# solar_charger_fuel_gauge_dev.net
KiCad netlist of a schematic drawn in EAGLE
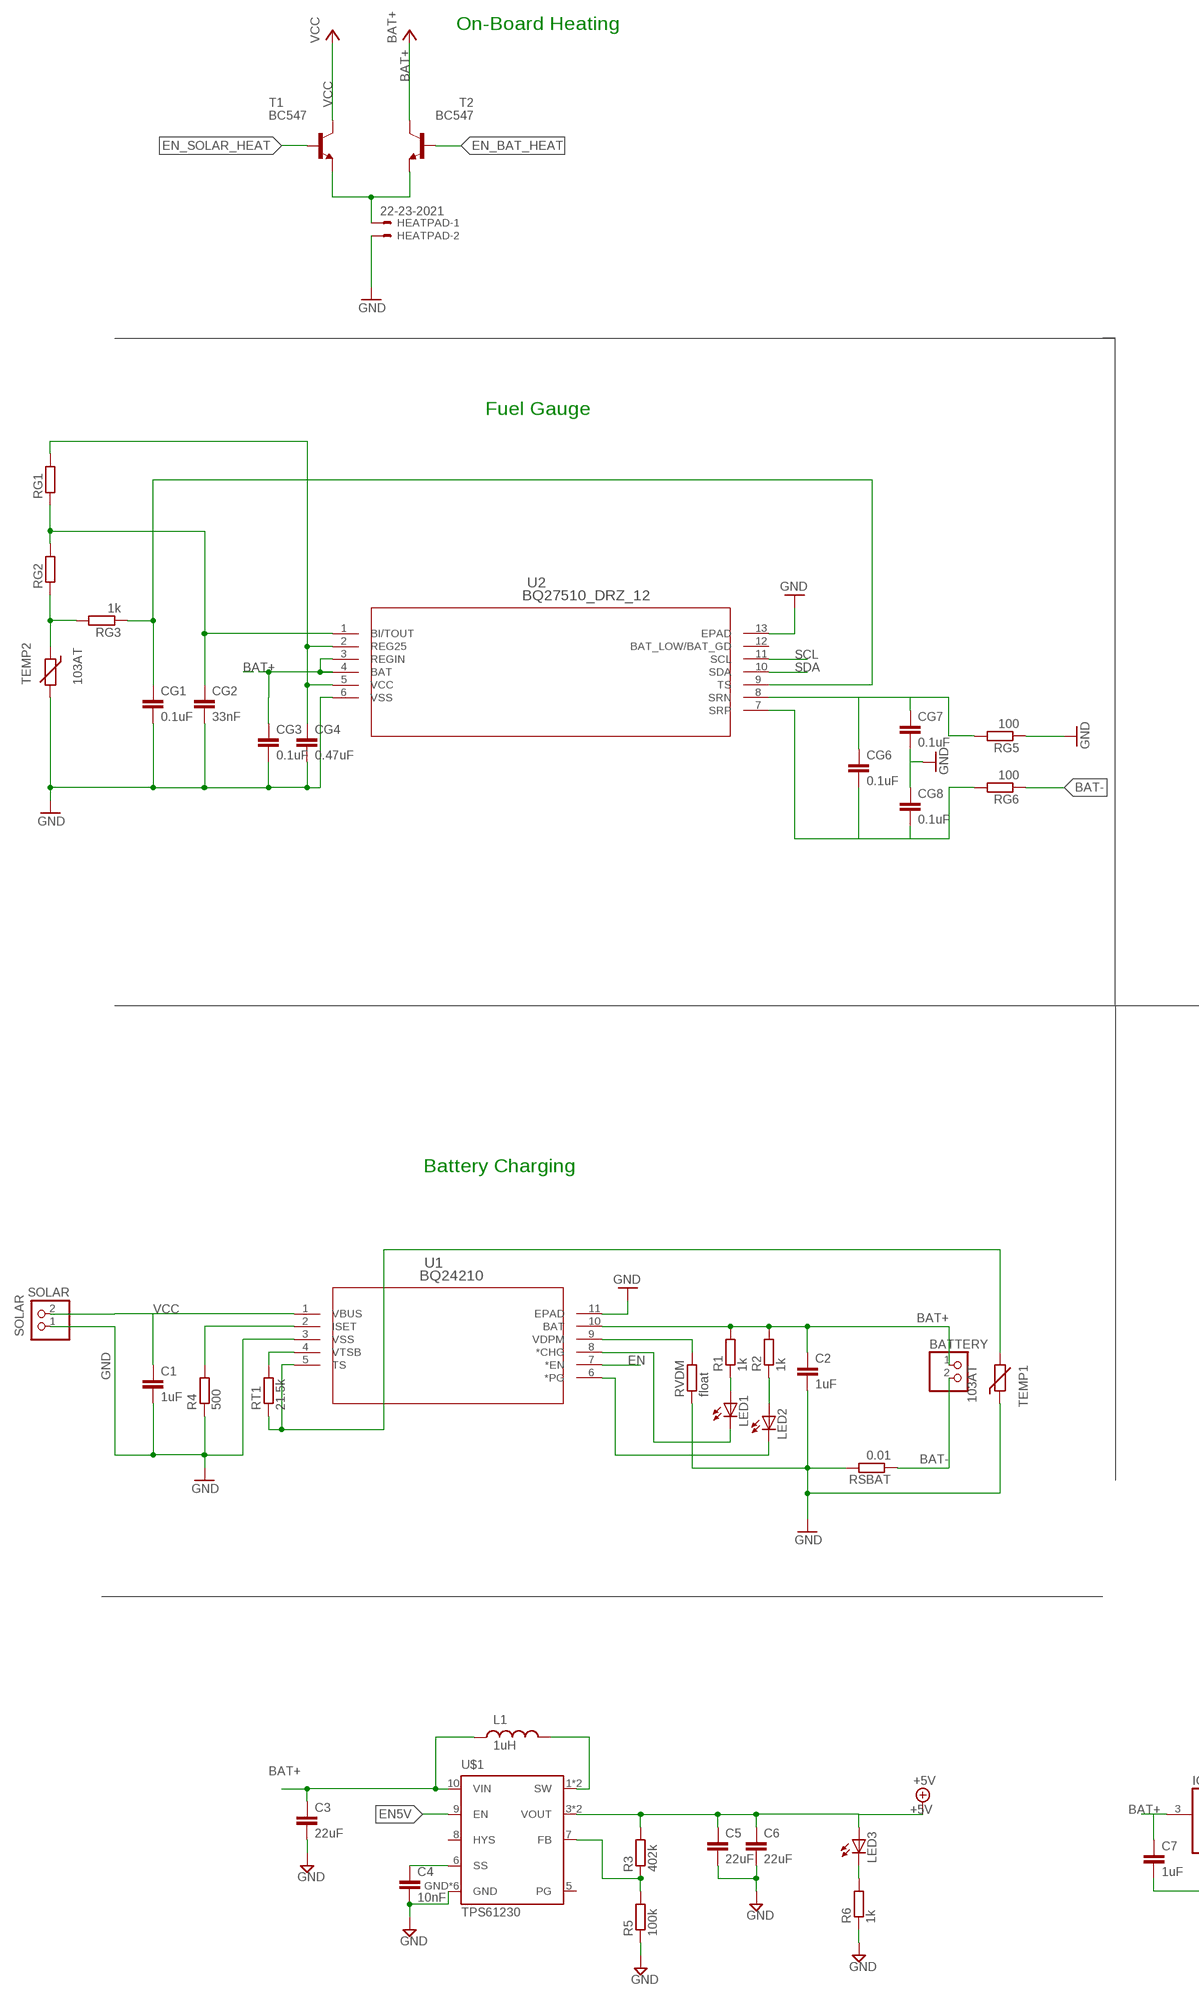
[diagram p0: schematic, sheet 1, part 1 of 3]
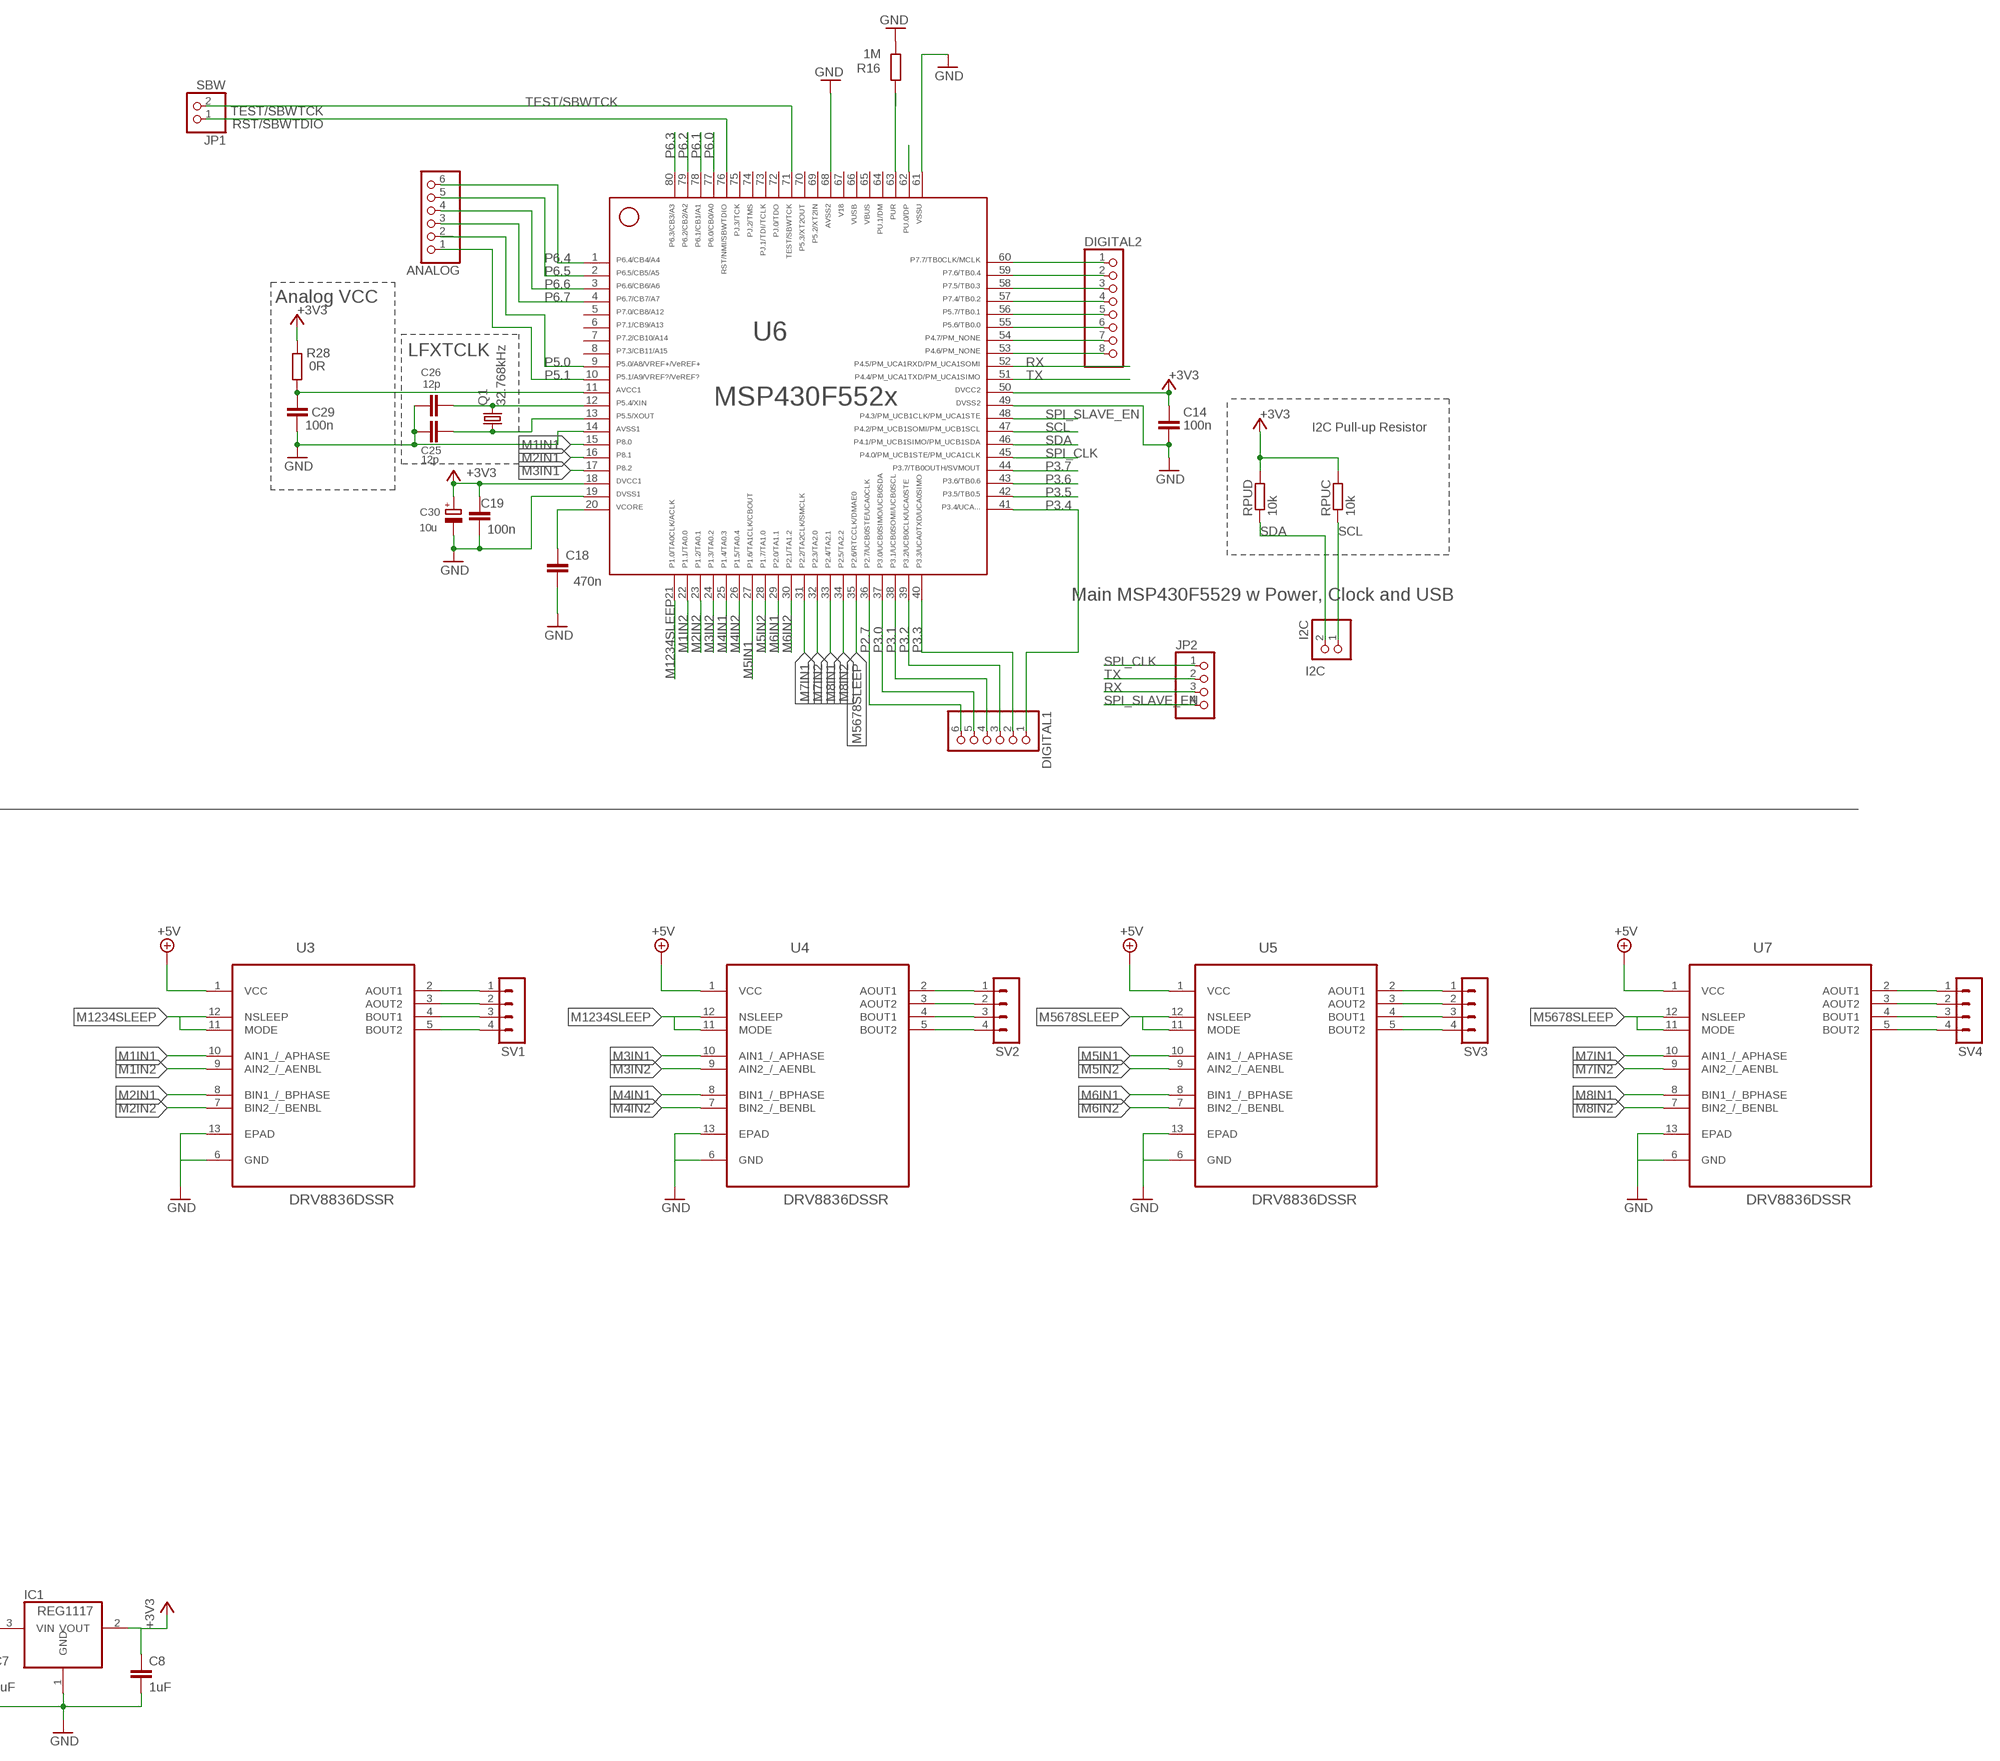
[diagram p1: schematic, sheet 1, part 2 of 3]
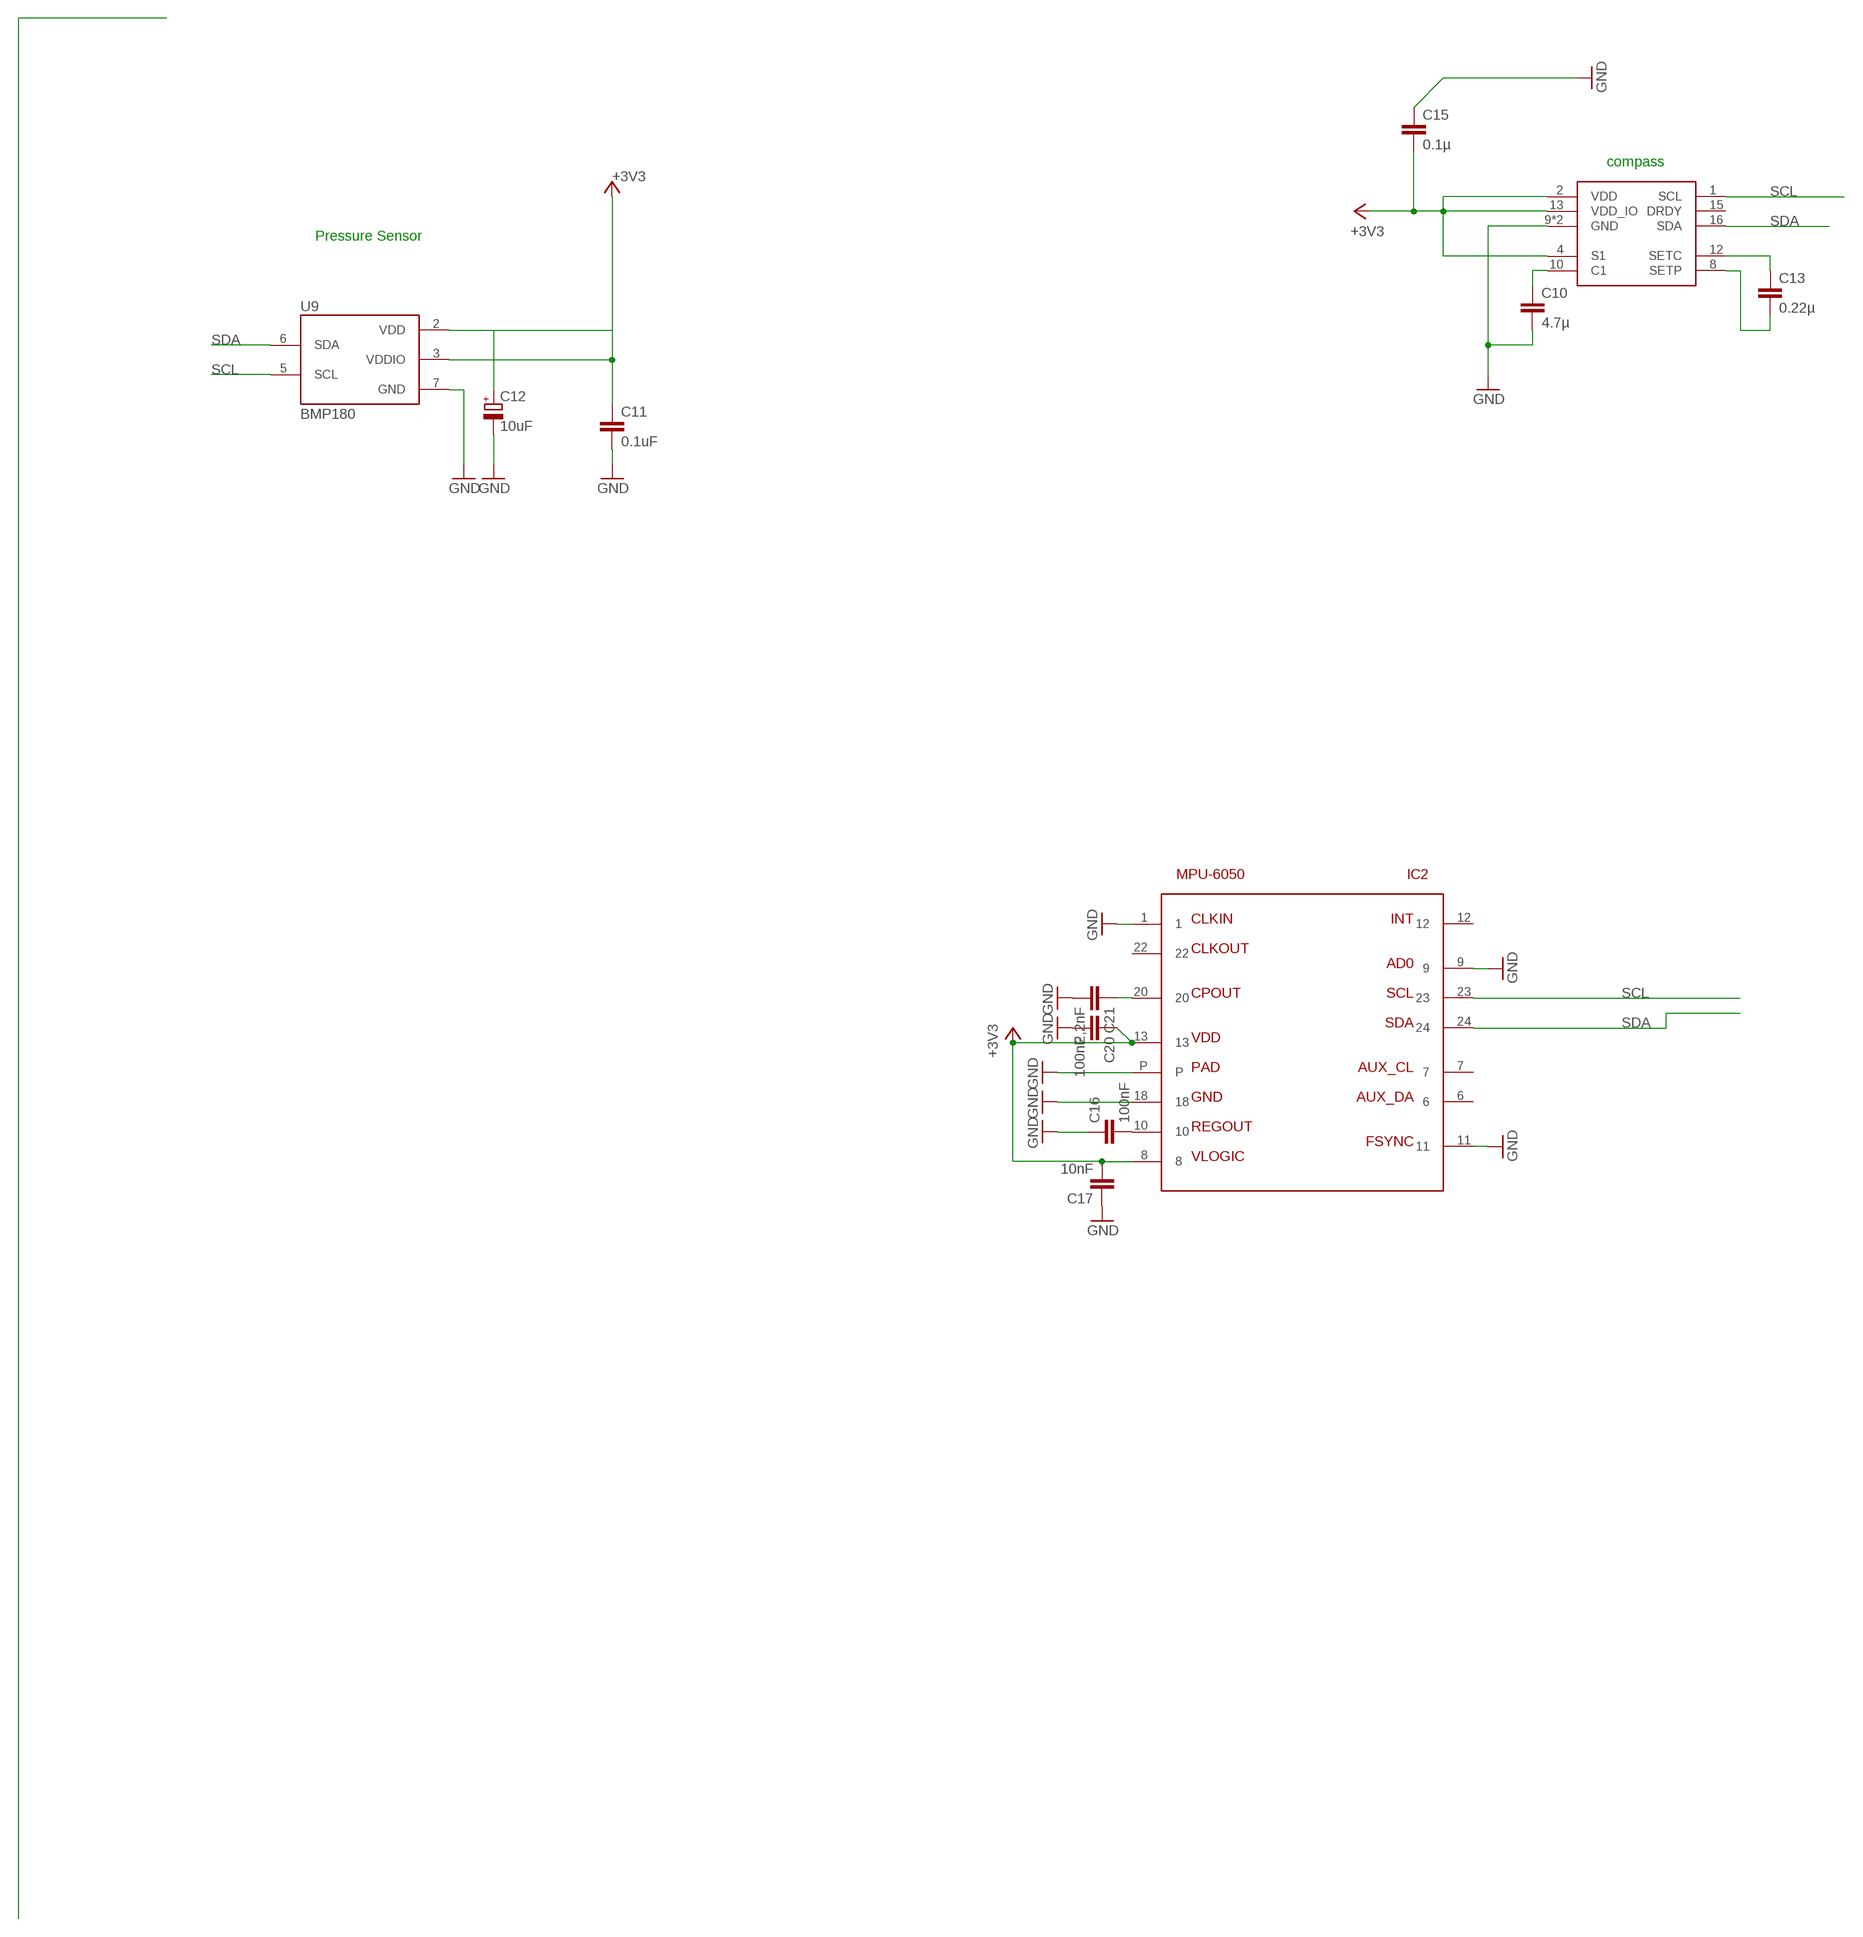
[diagram p2: schematic, sheet 1, part 3 of 3]

(export (version "E")
  (design (tool "Eeschema 10.0.6"))
  (components
    (comp (ref "ANALOG")
      (value "PINHD-1X6")
      (footprint "eagle-import:1X06")
      (libsource (lib "eagle-import") (part "PINHD-1X6"))
    )
    (comp (ref "BATTERY")
      (value "PINHD-1X2")
      (footprint "eagle-import:1X02")
      (libsource (lib "eagle-import") (part "PINHD-1X2"))
    )
    (comp (ref "C1")
      (value "1uF")
      (footprint "eagle-import:C1206")
      (libsource (lib "eagle-import") (part "C-EUC1206"))
    )
    (comp (ref "C2")
      (value "1uF")
      (footprint "eagle-import:C1206")
      (libsource (lib "eagle-import") (part "C-EUC1206"))
    )
    (comp (ref "C3")
      (value "22uF")
      (footprint "eagle-import:C0603")
      (libsource (lib "eagle-import") (part "C-EUC0603"))
    )
    (comp (ref "C4")
      (value "10nF")
      (footprint "eagle-import:C0603")
      (libsource (lib "eagle-import") (part "C-EUC0603"))
    )
    (comp (ref "C5")
      (value "22uF")
      (footprint "eagle-import:C0603")
      (libsource (lib "eagle-import") (part "C-EUC0603"))
    )
    (comp (ref "C6")
      (value "22uF")
      (footprint "eagle-import:C0603")
      (libsource (lib "eagle-import") (part "C-EUC0603"))
    )
    (comp (ref "C7")
      (value "1uF")
      (footprint "eagle-import:C0603")
      (libsource (lib "eagle-import") (part "C-EUC0603"))
    )
    (comp (ref "C8")
      (value "1uF")
      (footprint "eagle-import:C0603")
      (libsource (lib "eagle-import") (part "C-EUC0603"))
    )
    (comp (ref "C10")
      (value "4.7µ")
      (footprint "eagle-import:C0603")
      (libsource (lib "eagle-import") (part "C-EUC0603"))
    )
    (comp (ref "C11")
      (value "0.1uF")
      (footprint "eagle-import:C0603")
      (libsource (lib "eagle-import") (part "C-EUC0603"))
    )
    (comp (ref "C12")
      (value "10uF")
      (footprint "eagle-import:A_3216-18R")
      (libsource (lib "eagle-import") (part "resistor_CPOL-EUA/3216-18R"))
    )
    (comp (ref "C13")
      (value "0.22µ")
      (footprint "eagle-import:C0603")
      (libsource (lib "eagle-import") (part "C-EUC0603"))
    )
    (comp (ref "C14")
      (value "100n")
      (footprint "eagle-import:C0603")
      (libsource (lib "eagle-import") (part "C-EUC0603"))
    )
    (comp (ref "C15")
      (value "0.1µ")
      (footprint "eagle-import:C0603")
      (libsource (lib "eagle-import") (part "C-EUC0603"))
    )
    (comp (ref "C16")
      (value "100nF")
      (footprint "eagle-import:C0603")
      (libsource (lib "eagle-import") (part "C-EUC0603"))
    )
    (comp (ref "C17")
      (value "10nF")
      (footprint "eagle-import:C0603")
      (libsource (lib "eagle-import") (part "C-EUC0603"))
    )
    (comp (ref "C18")
      (value "470n")
      (footprint "eagle-import:C0603")
      (libsource (lib "eagle-import") (part "C-EUC0603"))
    )
    (comp (ref "C19")
      (value "100n")
      (footprint "eagle-import:C0603")
      (libsource (lib "eagle-import") (part "C-EUC0603"))
    )
    (comp (ref "C20")
      (value "100nF")
      (footprint "eagle-import:C0603")
      (libsource (lib "eagle-import") (part "C-EUC0603"))
    )
    (comp (ref "C21")
      (value "2,2nF")
      (footprint "eagle-import:C0603")
      (libsource (lib "eagle-import") (part "C-EUC0603"))
    )
    (comp (ref "C25")
      (value "12p")
      (footprint "eagle-import:C0603")
      (libsource (lib "eagle-import") (part "C-EUC0603"))
    )
    (comp (ref "C26")
      (value "12p")
      (footprint "eagle-import:C0603")
      (libsource (lib "eagle-import") (part "C-EUC0603"))
    )
    (comp (ref "C29")
      (value "100n")
      (footprint "eagle-import:C0603")
      (libsource (lib "eagle-import") (part "C-EUC0603"))
    )
    (comp (ref "C30")
      (value "10u")
      (footprint "eagle-import:A_3216-18R")
      (libsource (lib "eagle-import") (part "CPOL-EUA/3216-18R"))
    )
    (comp (ref "CG1")
      (value "0.1uF")
      (footprint "eagle-import:C0603")
      (libsource (lib "eagle-import") (part "C-EUC0603"))
    )
    (comp (ref "CG2")
      (value "33nF")
      (footprint "eagle-import:C0603")
      (libsource (lib "eagle-import") (part "C-EUC0603"))
    )
    (comp (ref "CG3")
      (value "0.1uF")
      (footprint "eagle-import:C0603")
      (libsource (lib "eagle-import") (part "C-EUC0603"))
    )
    (comp (ref "CG4")
      (value "0.47uF")
      (footprint "eagle-import:C0603")
      (libsource (lib "eagle-import") (part "C-EUC0603"))
    )
    (comp (ref "CG6")
      (value "0.1uF")
      (footprint "eagle-import:C0603")
      (libsource (lib "eagle-import") (part "C-EUC0603"))
    )
    (comp (ref "CG7")
      (value "0.1uF")
      (footprint "eagle-import:C0603")
      (libsource (lib "eagle-import") (part "C-EUC0603"))
    )
    (comp (ref "CG8")
      (value "0.1uF")
      (footprint "eagle-import:C0603")
      (libsource (lib "eagle-import") (part "C-EUC0603"))
    )
    (comp (ref "COMPASS")
      (value "HMC5883L")
      (footprint "eagle-import:LPCC16")
      (libsource (lib "eagle-import") (part "HMC5883L"))
    )
    (comp (ref "DIGITAL1")
      (value "PINHD-1X6")
      (footprint "eagle-import:1X06")
      (libsource (lib "eagle-import") (part "PINHD-1X6"))
    )
    (comp (ref "DIGITAL2")
      (value "PINHD-1X8")
      (footprint "eagle-import:1X08")
      (libsource (lib "eagle-import") (part "PINHD-1X8"))
    )
    (comp (ref "HEATPAD")
      (value "22-23-2021")
      (footprint "eagle-import:22-23-2021")
      (fields (field (name "MF") "MOLEX"))
      (libsource (lib "eagle-import") (part "22-23-2021"))
    )
    (comp (ref "I2C")
      (value "I2C")
      (footprint "eagle-import:1X02")
      (libsource (lib "eagle-import") (part "PINHD-1X2"))
    )
    (comp (ref "IC1")
      (value "REG1117")
      (footprint "eagle-import:SOT223")
      (libsource (lib "eagle-import") (part "REG1117"))
    )
    (comp (ref "IC2")
      (value "MPU-6050")
      (footprint "eagle-import:QFN24")
      (libsource (lib "eagle-import") (part "MPU-6050"))
    )
    (comp (ref "JP1")
      (value "SBW")
      (footprint "eagle-import:1X02")
      (libsource (lib "eagle-import") (part "PINHD-1X2"))
    )
    (comp (ref "JP2")
      (value "PINHD-1X4")
      (footprint "eagle-import:1X04")
      (libsource (lib "eagle-import") (part "PINHD-1X4"))
    )
    (comp (ref "L1")
      (value "1uH")
      (footprint "eagle-import:XFL4020")
      (libsource (lib "eagle-import") (part "XFL4020"))
    )
    (comp (ref "LED1")
      (value "LEDCHIP-LED0603")
      (footprint "eagle-import:CHIP-LED0603")
      (libsource (lib "eagle-import") (part "led_LEDCHIP-LED0603"))
    )
    (comp (ref "LED2")
      (value "LEDCHIP-LED0603")
      (footprint "eagle-import:CHIP-LED0603")
      (libsource (lib "eagle-import") (part "led_LEDCHIP-LED0603"))
    )
    (comp (ref "LED3")
      (value "LEDCHIPLED_0603")
      (footprint "eagle-import:CHIPLED_0603")
      (libsource (lib "eagle-import") (part "LEDCHIPLED_0603"))
    )
    (comp (ref "Q1")
      (value "32.768kHz")
      (footprint "eagle-import:FC-12M")
      (libsource (lib "eagle-import") (part "FC-12M"))
    )
    (comp (ref "R1")
      (value "1k")
      (footprint "eagle-import:R0603")
      (libsource (lib "eagle-import") (part "R-EU_R0603"))
    )
    (comp (ref "R2")
      (value "1k")
      (footprint "eagle-import:R0603")
      (libsource (lib "eagle-import") (part "R-EU_R0603"))
    )
    (comp (ref "R3")
      (value "402k")
      (footprint "eagle-import:R0603")
      (libsource (lib "eagle-import") (part "R-EU_R0603"))
    )
    (comp (ref "R4")
      (value "500")
      (footprint "eagle-import:R1206")
      (libsource (lib "eagle-import") (part "resistor_R-EU_R1206"))
    )
    (comp (ref "R5")
      (value "100k")
      (footprint "eagle-import:R0603")
      (libsource (lib "eagle-import") (part "R-EU_R0603"))
    )
    (comp (ref "R6")
      (value "1k")
      (footprint "eagle-import:R0603")
      (libsource (lib "eagle-import") (part "R-EU_R0603"))
    )
    (comp (ref "R16")
      (value "1M")
      (footprint "eagle-import:R0603")
      (libsource (lib "eagle-import") (part "R-EU_R0603"))
    )
    (comp (ref "R28")
      (value "0R")
      (footprint "eagle-import:R0603")
      (libsource (lib "eagle-import") (part "R-EU_R0603"))
    )
    (comp (ref "RG1")
      (value "R-EU_R0603")
      (footprint "eagle-import:R0603")
      (libsource (lib "eagle-import") (part "R-EU_R0603"))
    )
    (comp (ref "RG2")
      (value "R-EU_R0603")
      (footprint "eagle-import:R0603")
      (libsource (lib "eagle-import") (part "R-EU_R0603"))
    )
    (comp (ref "RG3")
      (value "1k")
      (footprint "eagle-import:R0603")
      (libsource (lib "eagle-import") (part "R-EU_R0603"))
    )
    (comp (ref "RG5")
      (value "100")
      (footprint "eagle-import:R0603")
      (libsource (lib "eagle-import") (part "R-EU_R0603"))
    )
    (comp (ref "RG6")
      (value "100")
      (footprint "eagle-import:R0603")
      (libsource (lib "eagle-import") (part "R-EU_R0603"))
    )
    (comp (ref "RPUC")
      (value "10k")
      (footprint "eagle-import:R0603")
      (libsource (lib "eagle-import") (part "R-EU_R0603"))
    )
    (comp (ref "RPUD")
      (value "10k")
      (footprint "eagle-import:R0603")
      (libsource (lib "eagle-import") (part "R-EU_R0603"))
    )
    (comp (ref "RSBAT")
      (value "0.01")
      (footprint "eagle-import:R1206")
      (libsource (lib "eagle-import") (part "resistor_R-EU_R1206"))
    )
    (comp (ref "RT1")
      (value "21.5k")
      (footprint "eagle-import:R1206")
      (libsource (lib "eagle-import") (part "resistor_R-EU_R1206"))
    )
    (comp (ref "RVDM")
      (value "float")
      (footprint "eagle-import:R1206")
      (libsource (lib "eagle-import") (part "resistor_R-EU_R1206"))
    )
    (comp (ref "SOLAR")
      (value "SOLAR")
      (footprint "eagle-import:1X02")
      (libsource (lib "eagle-import") (part "PINHD-1X2"))
    )
    (comp (ref "SV1")
      (value "MA04-1")
      (footprint "eagle-import:MA04-1")
      (libsource (lib "eagle-import") (part "MA04-1"))
    )
    (comp (ref "SV2")
      (value "MA04-1")
      (footprint "eagle-import:MA04-1")
      (libsource (lib "eagle-import") (part "MA04-1"))
    )
    (comp (ref "SV3")
      (value "MA04-1")
      (footprint "eagle-import:MA04-1")
      (libsource (lib "eagle-import") (part "MA04-1"))
    )
    (comp (ref "SV4")
      (value "MA04-1")
      (footprint "eagle-import:MA04-1")
      (libsource (lib "eagle-import") (part "MA04-1"))
    )
    (comp (ref "T1")
      (value "BC547")
      (footprint "eagle-import:TO92")
      (libsource (lib "eagle-import") (part "BC547"))
    )
    (comp (ref "T2")
      (value "BC547")
      (footprint "eagle-import:TO92")
      (libsource (lib "eagle-import") (part "BC547"))
    )
    (comp (ref "TEMP1")
      (value "103AT")
      (footprint "eagle-import:RS-2,5")
      (libsource (lib "eagle-import") (part "THERMISTOR-2,5"))
    )
    (comp (ref "TEMP2")
      (value "103AT")
      (footprint "eagle-import:RS-2,5")
      (libsource (lib "eagle-import") (part "THERMISTOR-2,5"))
    )
    (comp (ref "U$1")
      (value "TPS61230")
      (footprint "eagle-import:DRC-S-PVSON-N11")
      (libsource (lib "eagle-import") (part "TPS61230"))
    )
    (comp (ref "U1")
      (value "BQ24210")
      (footprint "eagle-import:DQC10_P84X2P4")
      (fields (field (name "MANUFACTURER") "Texas Instruments"))
      (libsource (lib "eagle-import") (part "BQ24210_DQC_10"))
    )
    (comp (ref "U2")
      (value "BQ27510_DRZ_12")
      (footprint "eagle-import:DRZ12_1P95X2P45")
      (fields
        (field (name "GENERIC_PART_NUMBER") "BQ27510")
        (field (name "MANUFACTURER") "Texas Instruments")
      )
      (libsource (lib "eagle-import") (part "BQ27510_DRZ_12"))
    )
    (comp (ref "U3")
      (value "DRV8836DSSR")
      (footprint "eagle-import:SON50P200X300X80-13N")
      (fields (field (name "MPN") "DRV8836DSSR "))
      (libsource (lib "eagle-import") (part "DRV8836DSSR"))
    )
    (comp (ref "U4")
      (value "DRV8836DSSR")
      (footprint "eagle-import:SON50P200X300X80-13N")
      (fields (field (name "MPN") "DRV8836DSSR "))
      (libsource (lib "eagle-import") (part "DRV8836DSSR"))
    )
    (comp (ref "U5")
      (value "DRV8836DSSR")
      (footprint "eagle-import:SON50P200X300X80-13N")
      (fields (field (name "MPN") "DRV8836DSSR "))
      (libsource (lib "eagle-import") (part "DRV8836DSSR"))
    )
    (comp (ref "U6")
      (value "MSP430F5529IPNR")
      (footprint "eagle-import:PN80")
      (libsource (lib "eagle-import") (part "F552X---PN80"))
    )
    (comp (ref "U7")
      (value "DRV8836DSSR")
      (footprint "eagle-import:SON50P200X300X80-13N")
      (fields (field (name "MPN") "DRV8836DSSR "))
      (libsource (lib "eagle-import") (part "DRV8836DSSR"))
    )
    (comp (ref "U9")
      (value "BMP180")
      (footprint "eagle-import:BMP180")
      (libsource (lib "eagle-import") (part "BMP180"))
    )
  )
  (nets
    (net (code "1") (name "+3V3") (class "Default")
      (node (ref "C11") (pin "1") (pinfunction "1_1") (pintype "passive"))
      (node (ref "C12") (pin "+") (pinfunction "+_+") (pintype "passive"))
      (node (ref "C14") (pin "1") (pinfunction "1_1") (pintype "passive"))
      (node (ref "C15") (pin "2") (pinfunction "2_2") (pintype "passive"))
      (node (ref "C17") (pin "2") (pinfunction "2_2") (pintype "passive"))
      (node (ref "C19") (pin "2") (pinfunction "2_2") (pintype "passive"))
      (node (ref "C20") (pin "1") (pinfunction "1_1") (pintype "passive"))
      (node (ref "C30") (pin "+") (pinfunction "+_+") (pintype "passive"))
      (node (ref "C8") (pin "1") (pinfunction "1_1") (pintype "passive"))
      (node (ref "COMPASS") (pin "13") (pinfunction "VDD_IO_13") (pintype "power_in"))
      (node (ref "COMPASS") (pin "2") (pinfunction "VDD_2") (pintype "power_in"))
      (node (ref "COMPASS") (pin "4") (pinfunction "S1_4") (pintype "power_in"))
      (node (ref "IC1") (pin "2") (pinfunction "VOUT_2") (pintype "output"))
      (node (ref "IC2") (pin "13") (pinfunction "13_13") (pintype "bidirectional"))
      (node (ref "IC2") (pin "8") (pinfunction "8_8") (pintype "bidirectional"))
      (node (ref "R28") (pin "2") (pinfunction "2_2") (pintype "passive"))
      (node (ref "RPUC") (pin "2") (pinfunction "2_2") (pintype "passive"))
      (node (ref "RPUD") (pin "2") (pinfunction "2_2") (pintype "passive"))
      (node (ref "U6") (pin "18") (pinfunction "18_18") (pintype "power_in"))
      (node (ref "U6") (pin "50") (pinfunction "50_50") (pintype "power_in"))
      (node (ref "U9") (pin "2") (pinfunction "VDD_2") (pintype "power_in"))
      (node (ref "U9") (pin "3") (pinfunction "VDDIO_3") (pintype "power_in"))
    )
    (net (code "2") (name "+5V") (class "Default")
      (node (ref "C5") (pin "1") (pinfunction "1_1") (pintype "passive"))
      (node (ref "C6") (pin "1") (pinfunction "1_1") (pintype "passive"))
      (node (ref "LED3") (pin "A") (pinfunction "A_A") (pintype "passive"))
      (node (ref "R3") (pin "2") (pinfunction "2_2") (pintype "passive"))
      (node (ref "U$1") (pin "3") (pinfunction "VOUT_3") (pintype "passive"))
      (node (ref "U$1") (pin "4") (pinfunction "VOUT_4") (pintype "passive"))
      (node (ref "U3") (pin "1") (pinfunction "VCC_1") (pintype "power_in"))
      (node (ref "U4") (pin "1") (pinfunction "VCC_1") (pintype "power_in"))
      (node (ref "U5") (pin "1") (pinfunction "VCC_1") (pintype "power_in"))
      (node (ref "U7") (pin "1") (pinfunction "VCC_1") (pintype "power_in"))
    )
    (net (code "3") (name "/65") (class "Default")
      (node (ref "U6") (pin "65") (pinfunction "65_65") (pintype "power_in"))
    )
    (net (code "4") (name "/66") (class "Default")
      (node (ref "U6") (pin "66") (pinfunction "66_66") (pintype "power_in"))
    )
    (net (code "5") (name "/67") (class "Default")
      (node (ref "U6") (pin "67") (pinfunction "67_67") (pintype "power_in"))
    )
    (net (code "6") (name "/EN") (class "Default")
      (node (ref "U1") (pin "7") (pinfunction "*EN_7") (pintype "input"))
    )
    (net (code "7") (name "/P2.7") (class "Default")
      (node (ref "DIGITAL1") (pin "6") (pinfunction "6_6") (pintype "passive"))
      (node (ref "U6") (pin "36") (pinfunction "36_36") (pintype "bidirectional"))
    )
    (net (code "8") (name "/P3.0") (class "Default")
      (node (ref "DIGITAL1") (pin "5") (pinfunction "5_5") (pintype "passive"))
      (node (ref "U6") (pin "37") (pinfunction "37_37") (pintype "bidirectional"))
    )
    (net (code "9") (name "/P3.1") (class "Default")
      (node (ref "DIGITAL1") (pin "4") (pinfunction "4_4") (pintype "passive"))
      (node (ref "U6") (pin "38") (pinfunction "38_38") (pintype "bidirectional"))
    )
    (net (code "10") (name "/P3.2") (class "Default")
      (node (ref "DIGITAL1") (pin "3") (pinfunction "3_3") (pintype "passive"))
      (node (ref "U6") (pin "39") (pinfunction "39_39") (pintype "bidirectional"))
    )
    (net (code "11") (name "/P3.3") (class "Default")
      (node (ref "DIGITAL1") (pin "2") (pinfunction "2_2") (pintype "passive"))
      (node (ref "U6") (pin "40") (pinfunction "40_40") (pintype "bidirectional"))
    )
    (net (code "12") (name "/P3.4") (class "Default")
      (node (ref "DIGITAL1") (pin "1") (pinfunction "1_1") (pintype "passive"))
      (node (ref "U6") (pin "41") (pinfunction "41_41") (pintype "bidirectional"))
    )
    (net (code "13") (name "/P3.5") (class "Default")
      (node (ref "U6") (pin "42") (pinfunction "42_42") (pintype "bidirectional"))
    )
    (net (code "14") (name "/P3.6") (class "Default")
      (node (ref "U6") (pin "43") (pinfunction "43_43") (pintype "bidirectional"))
    )
    (net (code "15") (name "/P3.7") (class "Default")
      (node (ref "U6") (pin "44") (pinfunction "44_44") (pintype "bidirectional"))
    )
    (net (code "16") (name "/P5.0") (class "Default")
      (node (ref "ANALOG") (pin "2") (pinfunction "2_2") (pintype "passive"))
      (node (ref "U6") (pin "9") (pinfunction "9_9") (pintype "bidirectional"))
    )
    (net (code "17") (name "/P5.1") (class "Default")
      (node (ref "ANALOG") (pin "1") (pinfunction "1_1") (pintype "passive"))
      (node (ref "U6") (pin "10") (pinfunction "10_10") (pintype "bidirectional"))
    )
    (net (code "18") (name "/P6.0") (class "Default")
      (node (ref "U6") (pin "77") (pinfunction "77_77") (pintype "bidirectional"))
    )
    (net (code "19") (name "/P6.1") (class "Default")
      (node (ref "U6") (pin "78") (pinfunction "78_78") (pintype "bidirectional"))
    )
    (net (code "20") (name "/P6.2") (class "Default")
      (node (ref "U6") (pin "79") (pinfunction "79_79") (pintype "bidirectional"))
    )
    (net (code "21") (name "/P6.3") (class "Default")
      (node (ref "U6") (pin "80") (pinfunction "80_80") (pintype "bidirectional"))
    )
    (net (code "22") (name "/P6.4") (class "Default")
      (node (ref "ANALOG") (pin "6") (pinfunction "6_6") (pintype "passive"))
      (node (ref "U6") (pin "1") (pinfunction "1_1") (pintype "bidirectional"))
    )
    (net (code "23") (name "/P6.5") (class "Default")
      (node (ref "ANALOG") (pin "5") (pinfunction "5_5") (pintype "passive"))
      (node (ref "U6") (pin "2") (pinfunction "2_2") (pintype "bidirectional"))
    )
    (net (code "24") (name "/P6.6") (class "Default")
      (node (ref "ANALOG") (pin "4") (pinfunction "4_4") (pintype "passive"))
      (node (ref "U6") (pin "3") (pinfunction "3_3") (pintype "bidirectional"))
    )
    (net (code "25") (name "/P6.7") (class "Default")
      (node (ref "ANALOG") (pin "3") (pinfunction "3_3") (pintype "passive"))
      (node (ref "U6") (pin "4") (pinfunction "4_4") (pintype "bidirectional"))
    )
    (net (code "26") (name "/PG") (class "Default")
      (node (ref "U$1") (pin "5") (pinfunction "PG_5") (pintype "power_in"))
    )
    (net (code "27") (name "/RST{slash}SBWTDIO") (class "Default")
      (node (ref "JP1") (pin "1") (pinfunction "1_1") (pintype "passive"))
      (node (ref "U6") (pin "76") (pinfunction "76_76") (pintype "bidirectional"))
    )
    (net (code "28") (name "/RX") (class "Default")
      (node (ref "JP2") (pin "3") (pinfunction "3_3") (pintype "passive"))
      (node (ref "U6") (pin "52") (pinfunction "52_52") (pintype "bidirectional"))
    )
    (net (code "29") (name "/SCL") (class "Default")
      (node (ref "COMPASS") (pin "1") (pinfunction "SCL_1") (pintype "input"))
      (node (ref "I2C") (pin "1") (pinfunction "1_1") (pintype "passive"))
      (node (ref "IC2") (pin "23") (pinfunction "23_23") (pintype "bidirectional"))
      (node (ref "RPUC") (pin "1") (pinfunction "1_1") (pintype "passive"))
      (node (ref "U2") (pin "11") (pinfunction "SCL_11") (pintype "input"))
      (node (ref "U6") (pin "47") (pinfunction "47_47") (pintype "bidirectional"))
      (node (ref "U9") (pin "5") (pinfunction "SCL_5") (pintype "input"))
    )
    (net (code "30") (name "/SDA") (class "Default")
      (node (ref "COMPASS") (pin "16") (pinfunction "SDA_16") (pintype "input"))
      (node (ref "I2C") (pin "2") (pinfunction "2_2") (pintype "passive"))
      (node (ref "IC2") (pin "24") (pinfunction "24_24") (pintype "bidirectional"))
      (node (ref "RPUD") (pin "1") (pinfunction "1_1") (pintype "passive"))
      (node (ref "U2") (pin "10") (pinfunction "SDA_10") (pintype "bidirectional"))
      (node (ref "U6") (pin "46") (pinfunction "46_46") (pintype "bidirectional"))
      (node (ref "U9") (pin "6") (pinfunction "SDA_6") (pintype "bidirectional"))
    )
    (net (code "31") (name "/SPI_CLK") (class "Default")
      (node (ref "JP2") (pin "1") (pinfunction "1_1") (pintype "passive"))
      (node (ref "U6") (pin "45") (pinfunction "45_45") (pintype "bidirectional"))
    )
    (net (code "32") (name "/SPI_SLAVE_EN") (class "Default")
      (node (ref "JP2") (pin "4") (pinfunction "4_4") (pintype "passive"))
      (node (ref "U6") (pin "48") (pinfunction "48_48") (pintype "bidirectional"))
    )
    (net (code "33") (name "/TEST{slash}SBWTCK") (class "Default")
      (node (ref "JP1") (pin "2") (pinfunction "2_2") (pintype "passive"))
      (node (ref "U6") (pin "71") (pinfunction "71_71") (pintype "input"))
    )
    (net (code "34") (name "/TX") (class "Default")
      (node (ref "JP2") (pin "2") (pinfunction "2_2") (pintype "passive"))
      (node (ref "U6") (pin "51") (pinfunction "51_51") (pintype "bidirectional"))
    )
    (net (code "35") (name "BAT+") (class "Default")
      (node (ref "BATTERY") (pin "1") (pinfunction "1_1") (pintype "passive"))
      (node (ref "C2") (pin "1") (pinfunction "1_1") (pintype "passive"))
      (node (ref "C3") (pin "1") (pinfunction "1_1") (pintype "passive"))
      (node (ref "C7") (pin "1") (pinfunction "1_1") (pintype "passive"))
      (node (ref "CG3") (pin "1") (pinfunction "1_1") (pintype "passive"))
      (node (ref "IC1") (pin "3") (pinfunction "VIN_3") (pintype "input"))
      (node (ref "L1") (pin "P$1") (pinfunction "1_P$1") (pintype "passive"))
      (node (ref "R1") (pin "2") (pinfunction "2_2") (pintype "passive"))
      (node (ref "R2") (pin "2") (pinfunction "2_2") (pintype "passive"))
      (node (ref "T2") (pin "3") (pinfunction "C_3") (pintype "passive"))
      (node (ref "U$1") (pin "10") (pinfunction "VIN_10") (pintype "input"))
      (node (ref "U1") (pin "10") (pinfunction "BAT_10") (pintype "bidirectional"))
      (node (ref "U2") (pin "3") (pinfunction "REGIN_3") (pintype "power_in"))
      (node (ref "U2") (pin "4") (pinfunction "BAT_4") (pintype "input"))
    )
    (net (code "36") (name "BAT-") (class "Default")
      (node (ref "BATTERY") (pin "2") (pinfunction "2_2") (pintype "passive"))
      (node (ref "RG6") (pin "1") (pinfunction "1_1") (pintype "passive"))
      (node (ref "RSBAT") (pin "1") (pinfunction "1_1") (pintype "passive"))
    )
    (net (code "37") (name "EN5V") (class "Default")
      (node (ref "U$1") (pin "9") (pinfunction "EN_9") (pintype "input"))
    )
    (net (code "38") (name "EN_BAT_HEAT") (class "Default")
      (node (ref "T2") (pin "2") (pinfunction "B_2") (pintype "passive"))
    )
    (net (code "39") (name "EN_SOLAR_HEAT") (class "Default")
      (node (ref "T1") (pin "2") (pinfunction "B_2") (pintype "passive"))
    )
    (net (code "40") (name "GND") (class "Default")
      (node (ref "C1") (pin "2") (pinfunction "2_2") (pintype "passive"))
      (node (ref "C10") (pin "2") (pinfunction "2_2") (pintype "passive"))
      (node (ref "C11") (pin "2") (pinfunction "2_2") (pintype "passive"))
      (node (ref "C12") (pin "-") (pinfunction "-_-") (pintype "passive"))
      (node (ref "C14") (pin "2") (pinfunction "2_2") (pintype "passive"))
      (node (ref "C15") (pin "1") (pinfunction "1_1") (pintype "passive"))
      (node (ref "C16") (pin "1") (pinfunction "1_1") (pintype "passive"))
      (node (ref "C17") (pin "1") (pinfunction "1_1") (pintype "passive"))
      (node (ref "C18") (pin "1") (pinfunction "1_1") (pintype "passive"))
      (node (ref "C19") (pin "1") (pinfunction "1_1") (pintype "passive"))
      (node (ref "C2") (pin "2") (pinfunction "2_2") (pintype "passive"))
      (node (ref "C20") (pin "2") (pinfunction "2_2") (pintype "passive"))
      (node (ref "C21") (pin "2") (pinfunction "2_2") (pintype "passive"))
      (node (ref "C25") (pin "1") (pinfunction "1_1") (pintype "passive"))
      (node (ref "C26") (pin "1") (pinfunction "1_1") (pintype "passive"))
      (node (ref "C29") (pin "2") (pinfunction "2_2") (pintype "passive"))
      (node (ref "C3") (pin "2") (pinfunction "2_2") (pintype "passive"))
      (node (ref "C30") (pin "-") (pinfunction "-_-") (pintype "passive"))
      (node (ref "C4") (pin "2") (pinfunction "2_2") (pintype "passive"))
      (node (ref "C5") (pin "2") (pinfunction "2_2") (pintype "passive"))
      (node (ref "C6") (pin "2") (pinfunction "2_2") (pintype "passive"))
      (node (ref "C7") (pin "2") (pinfunction "2_2") (pintype "passive"))
      (node (ref "C8") (pin "2") (pinfunction "2_2") (pintype "passive"))
      (node (ref "CG1") (pin "2") (pinfunction "2_2") (pintype "passive"))
      (node (ref "CG2") (pin "2") (pinfunction "2_2") (pintype "passive"))
      (node (ref "CG3") (pin "2") (pinfunction "2_2") (pintype "passive"))
      (node (ref "CG4") (pin "2") (pinfunction "2_2") (pintype "passive"))
      (node (ref "CG7") (pin "2") (pinfunction "2_2") (pintype "passive"))
      (node (ref "CG8") (pin "1") (pinfunction "1_1") (pintype "passive"))
      (node (ref "COMPASS") (pin "11") (pinfunction "GND_11") (pintype "bidirectional"))
      (node (ref "COMPASS") (pin "9") (pinfunction "GND_9") (pintype "bidirectional"))
      (node (ref "HEATPAD") (pin "2") (pinfunction "S_2") (pintype "passive"))
      (node (ref "IC1") (pin "1") (pinfunction "GND_1") (pintype "power_in"))
      (node (ref "IC2") (pin "1") (pinfunction "1_1") (pintype "bidirectional"))
      (node (ref "IC2") (pin "11") (pinfunction "11_11") (pintype "bidirectional"))
      (node (ref "IC2") (pin "18") (pinfunction "18_18") (pintype "bidirectional"))
      (node (ref "IC2") (pin "9") (pinfunction "9_9") (pintype "bidirectional"))
      (node (ref "IC2") (pin "P") (pinfunction "P_P") (pintype "bidirectional"))
      (node (ref "R16") (pin "1") (pinfunction "1_1") (pintype "passive"))
      (node (ref "R4") (pin "1") (pinfunction "1_1") (pintype "passive"))
      (node (ref "R5") (pin "1") (pinfunction "1_1") (pintype "passive"))
      (node (ref "R6") (pin "1") (pinfunction "1_1") (pintype "passive"))
      (node (ref "RG5") (pin "1") (pinfunction "1_1") (pintype "passive"))
      (node (ref "RSBAT") (pin "2") (pinfunction "2_2") (pintype "passive"))
      (node (ref "RVDM") (pin "1") (pinfunction "1_1") (pintype "passive"))
      (node (ref "SOLAR") (pin "1") (pinfunction "1_1") (pintype "passive"))
      (node (ref "TEMP1") (pin "1") (pinfunction "1_1") (pintype "passive"))
      (node (ref "TEMP2") (pin "2") (pinfunction "2_2") (pintype "passive"))
      (node (ref "U$1") (pin "GND") (pinfunction "GND_GND") (pintype "power_in"))
      (node (ref "U$1") (pin "GND@1") (pinfunction "GND_GND@1") (pintype "power_in"))
      (node (ref "U$1") (pin "GND@2") (pinfunction "GND_GND@2") (pintype "power_in"))
      (node (ref "U$1") (pin "GND@3") (pinfunction "GND_GND@3") (pintype "power_in"))
      (node (ref "U$1") (pin "GND@4") (pinfunction "GND_GND@4") (pintype "power_in"))
      (node (ref "U$1") (pin "GND@5") (pinfunction "GND_GND@5") (pintype "power_in"))
      (node (ref "U1") (pin "11") (pinfunction "EPAD_11") (pintype "power_in"))
      (node (ref "U1") (pin "3") (pinfunction "VSS_3") (pintype "power_in"))
      (node (ref "U2") (pin "13") (pinfunction "EPAD_13") (pintype "power_in"))
      (node (ref "U2") (pin "6") (pinfunction "VSS_6") (pintype "power_in"))
      (node (ref "U3") (pin "13") (pinfunction "EPAD_13") (pintype "passive"))
      (node (ref "U3") (pin "6") (pinfunction "GND_6") (pintype "passive"))
      (node (ref "U4") (pin "13") (pinfunction "EPAD_13") (pintype "passive"))
      (node (ref "U4") (pin "6") (pinfunction "GND_6") (pintype "passive"))
      (node (ref "U5") (pin "13") (pinfunction "EPAD_13") (pintype "passive"))
      (node (ref "U5") (pin "6") (pinfunction "GND_6") (pintype "passive"))
      (node (ref "U6") (pin "14") (pinfunction "14_14") (pintype "power_in"))
      (node (ref "U6") (pin "19") (pinfunction "19_19") (pintype "power_in"))
      (node (ref "U6") (pin "49") (pinfunction "49_49") (pintype "power_in"))
      (node (ref "U6") (pin "61") (pinfunction "61_61") (pintype "power_in"))
      (node (ref "U6") (pin "68") (pinfunction "68_68") (pintype "power_in"))
      (node (ref "U7") (pin "13") (pinfunction "EPAD_13") (pintype "passive"))
      (node (ref "U7") (pin "6") (pinfunction "GND_6") (pintype "passive"))
      (node (ref "U9") (pin "7") (pinfunction "GND_7") (pintype "power_in"))
    )
    (net (code "41") (name "M1IN1") (class "Default")
      (node (ref "U3") (pin "10") (pinfunction "AIN1_/_APHASE_10") (pintype "input"))
      (node (ref "U6") (pin "15") (pinfunction "15_15") (pintype "bidirectional"))
    )
    (net (code "42") (name "M1IN2") (class "Default")
      (node (ref "U3") (pin "9") (pinfunction "AIN2_/_AENBL_9") (pintype "input"))
      (node (ref "U6") (pin "22") (pinfunction "22_22") (pintype "bidirectional"))
    )
    (net (code "43") (name "M2IN1") (class "Default")
      (node (ref "U3") (pin "8") (pinfunction "BIN1_/_BPHASE_8") (pintype "input"))
      (node (ref "U6") (pin "16") (pinfunction "16_16") (pintype "bidirectional"))
    )
    (net (code "44") (name "M2IN2") (class "Default")
      (node (ref "U3") (pin "7") (pinfunction "BIN2_/_BENBL_7") (pintype "input"))
      (node (ref "U6") (pin "23") (pinfunction "23_23") (pintype "bidirectional"))
    )
    (net (code "45") (name "M3IN1") (class "Default")
      (node (ref "U4") (pin "10") (pinfunction "AIN1_/_APHASE_10") (pintype "input"))
      (node (ref "U6") (pin "17") (pinfunction "17_17") (pintype "bidirectional"))
    )
    (net (code "46") (name "M3IN2") (class "Default")
      (node (ref "U4") (pin "9") (pinfunction "AIN2_/_AENBL_9") (pintype "input"))
      (node (ref "U6") (pin "24") (pinfunction "24_24") (pintype "bidirectional"))
    )
    (net (code "47") (name "M4IN1") (class "Default")
      (node (ref "U4") (pin "8") (pinfunction "BIN1_/_BPHASE_8") (pintype "input"))
      (node (ref "U6") (pin "25") (pinfunction "25_25") (pintype "bidirectional"))
    )
    (net (code "48") (name "M4IN2") (class "Default")
      (node (ref "U4") (pin "7") (pinfunction "BIN2_/_BENBL_7") (pintype "input"))
      (node (ref "U6") (pin "26") (pinfunction "26_26") (pintype "bidirectional"))
    )
    (net (code "49") (name "M5IN1") (class "Default")
      (node (ref "U5") (pin "10") (pinfunction "AIN1_/_APHASE_10") (pintype "input"))
      (node (ref "U6") (pin "27") (pinfunction "27_27") (pintype "bidirectional"))
    )
    (net (code "50") (name "M5IN2") (class "Default")
      (node (ref "U5") (pin "9") (pinfunction "AIN2_/_AENBL_9") (pintype "input"))
      (node (ref "U6") (pin "28") (pinfunction "28_28") (pintype "bidirectional"))
    )
    (net (code "51") (name "M6IN1") (class "Default")
      (node (ref "U5") (pin "8") (pinfunction "BIN1_/_BPHASE_8") (pintype "input"))
      (node (ref "U6") (pin "29") (pinfunction "29_29") (pintype "bidirectional"))
    )
    (net (code "52") (name "M6IN2") (class "Default")
      (node (ref "U5") (pin "7") (pinfunction "BIN2_/_BENBL_7") (pintype "input"))
      (node (ref "U6") (pin "30") (pinfunction "30_30") (pintype "bidirectional"))
    )
    (net (code "53") (name "M7IN1") (class "Default")
      (node (ref "U6") (pin "31") (pinfunction "31_31") (pintype "bidirectional"))
      (node (ref "U7") (pin "10") (pinfunction "AIN1_/_APHASE_10") (pintype "input"))
    )
    (net (code "54") (name "M7IN2") (class "Default")
      (node (ref "U6") (pin "32") (pinfunction "32_32") (pintype "bidirectional"))
      (node (ref "U7") (pin "9") (pinfunction "AIN2_/_AENBL_9") (pintype "input"))
    )
    (net (code "55") (name "M8IN1") (class "Default")
      (node (ref "U6") (pin "33") (pinfunction "33_33") (pintype "bidirectional"))
      (node (ref "U7") (pin "8") (pinfunction "BIN1_/_BPHASE_8") (pintype "input"))
    )
    (net (code "56") (name "M8IN2") (class "Default")
      (node (ref "U6") (pin "34") (pinfunction "34_34") (pintype "bidirectional"))
      (node (ref "U7") (pin "7") (pinfunction "BIN2_/_BENBL_7") (pintype "input"))
    )
    (net (code "57") (name "M1234SLEEP") (class "Default")
      (node (ref "U3") (pin "11") (pinfunction "MODE_11") (pintype "input"))
      (node (ref "U3") (pin "12") (pinfunction "NSLEEP_12") (pintype "input"))
      (node (ref "U4") (pin "11") (pinfunction "MODE_11") (pintype "input"))
      (node (ref "U4") (pin "12") (pinfunction "NSLEEP_12") (pintype "input"))
      (node (ref "U6") (pin "21") (pinfunction "21_21") (pintype "bidirectional"))
    )
    (net (code "58") (name "M5678SLEEP") (class "Default")
      (node (ref "U5") (pin "11") (pinfunction "MODE_11") (pintype "input"))
      (node (ref "U5") (pin "12") (pinfunction "NSLEEP_12") (pintype "input"))
      (node (ref "U6") (pin "35") (pinfunction "35_35") (pintype "bidirectional"))
      (node (ref "U7") (pin "11") (pinfunction "MODE_11") (pintype "input"))
      (node (ref "U7") (pin "12") (pinfunction "NSLEEP_12") (pintype "input"))
    )
    (net (code "59") (name "Net-(C16-Pad2)") (class "Default")
      (node (ref "C16") (pin "2") (pinfunction "2_2") (pintype "passive"))
      (node (ref "IC2") (pin "10") (pinfunction "10_10") (pintype "bidirectional"))
    )
    (net (code "60") (name "Net-(C18-Pad2)") (class "Default")
      (node (ref "C18") (pin "2") (pinfunction "2_2") (pintype "passive"))
      (node (ref "U6") (pin "20") (pinfunction "20_20") (pintype "power_in"))
    )
    (net (code "61") (name "Net-(C21-Pad1)") (class "Default")
      (node (ref "C21") (pin "1") (pinfunction "1_1") (pintype "passive"))
      (node (ref "IC2") (pin "20") (pinfunction "20_20") (pintype "bidirectional"))
    )
    (net (code "62") (name "Net-(C25-Pad2)") (class "Default")
      (node (ref "C25") (pin "2") (pinfunction "2_2") (pintype "passive"))
      (node (ref "Q1") (pin "1") (pinfunction "1_1") (pintype "passive"))
      (node (ref "U6") (pin "13") (pinfunction "13_13") (pintype "bidirectional"))
    )
    (net (code "63") (name "Net-(C26-Pad2)") (class "Default")
      (node (ref "C26") (pin "2") (pinfunction "2_2") (pintype "passive"))
      (node (ref "Q1") (pin "2") (pinfunction "2_2") (pintype "passive"))
      (node (ref "U6") (pin "12") (pinfunction "12_12") (pintype "bidirectional"))
    )
    (net (code "64") (name "Net-(C29-Pad1)") (class "Default")
      (node (ref "C29") (pin "1") (pinfunction "1_1") (pintype "passive"))
      (node (ref "R28") (pin "1") (pinfunction "1_1") (pintype "passive"))
      (node (ref "U6") (pin "11") (pinfunction "11_11") (pintype "power_in"))
    )
    (net (code "65") (name "Net-(COMPASS-C1)") (class "Default")
      (node (ref "C10") (pin "1") (pinfunction "1_1") (pintype "passive"))
      (node (ref "COMPASS") (pin "10") (pinfunction "C1_10") (pintype "passive"))
    )
    (net (code "66") (name "Net-(COMPASS-SETC)") (class "Default")
      (node (ref "C13") (pin "1") (pinfunction "1_1") (pintype "passive"))
      (node (ref "COMPASS") (pin "12") (pinfunction "SETC_12") (pintype "passive"))
    )
    (net (code "67") (name "Net-(COMPASS-SETP)") (class "Default")
      (node (ref "C13") (pin "2") (pinfunction "2_2") (pintype "passive"))
      (node (ref "COMPASS") (pin "8") (pinfunction "SETP_8") (pintype "passive"))
    )
    (net (code "68") (name "Net-(DIGITAL2-Pad1)") (class "Default")
      (node (ref "DIGITAL2") (pin "1") (pinfunction "1_1") (pintype "passive"))
      (node (ref "U6") (pin "60") (pinfunction "60_60") (pintype "bidirectional"))
    )
    (net (code "69") (name "Net-(DIGITAL2-Pad2)") (class "Default")
      (node (ref "DIGITAL2") (pin "2") (pinfunction "2_2") (pintype "passive"))
      (node (ref "U6") (pin "59") (pinfunction "59_59") (pintype "bidirectional"))
    )
    (net (code "70") (name "Net-(DIGITAL2-Pad3)") (class "Default")
      (node (ref "DIGITAL2") (pin "3") (pinfunction "3_3") (pintype "passive"))
      (node (ref "U6") (pin "58") (pinfunction "58_58") (pintype "bidirectional"))
    )
    (net (code "71") (name "Net-(DIGITAL2-Pad4)") (class "Default")
      (node (ref "DIGITAL2") (pin "4") (pinfunction "4_4") (pintype "passive"))
      (node (ref "U6") (pin "57") (pinfunction "57_57") (pintype "bidirectional"))
    )
    (net (code "72") (name "Net-(DIGITAL2-Pad5)") (class "Default")
      (node (ref "DIGITAL2") (pin "5") (pinfunction "5_5") (pintype "passive"))
      (node (ref "U6") (pin "56") (pinfunction "56_56") (pintype "bidirectional"))
    )
    (net (code "73") (name "Net-(DIGITAL2-Pad6)") (class "Default")
      (node (ref "DIGITAL2") (pin "6") (pinfunction "6_6") (pintype "passive"))
      (node (ref "U6") (pin "55") (pinfunction "55_55") (pintype "bidirectional"))
    )
    (net (code "74") (name "Net-(DIGITAL2-Pad7)") (class "Default")
      (node (ref "DIGITAL2") (pin "7") (pinfunction "7_7") (pintype "passive"))
      (node (ref "U6") (pin "54") (pinfunction "54_54") (pintype "bidirectional"))
    )
    (net (code "75") (name "Net-(DIGITAL2-Pad8)") (class "Default")
      (node (ref "DIGITAL2") (pin "8") (pinfunction "8_8") (pintype "passive"))
      (node (ref "U6") (pin "53") (pinfunction "53_53") (pintype "bidirectional"))
    )
    (net (code "76") (name "Net-(HEATPADA-S)") (class "Default")
      (node (ref "HEATPAD") (pin "1") (pinfunction "S_1") (pintype "passive"))
      (node (ref "T1") (pin "1") (pinfunction "E_1") (pintype "passive"))
      (node (ref "T2") (pin "1") (pinfunction "E_1") (pintype "passive"))
    )
    (net (code "77") (name "Net-(L1-2)") (class "Default")
      (node (ref "L1") (pin "P$2") (pinfunction "2_P$2") (pintype "passive"))
      (node (ref "U$1") (pin "1") (pinfunction "SW_1") (pintype "input"))
      (node (ref "U$1") (pin "2") (pinfunction "SW_2") (pintype "input"))
    )
    (net (code "78") (name "Net-(LED1-PadA)") (class "Default")
      (node (ref "LED1") (pin "A") (pinfunction "A_A") (pintype "passive"))
      (node (ref "R1") (pin "1") (pinfunction "1_1") (pintype "passive"))
    )
    (net (code "79") (name "Net-(LED2-PadA)") (class "Default")
      (node (ref "LED2") (pin "A") (pinfunction "A_A") (pintype "passive"))
      (node (ref "R2") (pin "1") (pinfunction "1_1") (pintype "passive"))
    )
    (net (code "80") (name "Net-(LED3-PadC)") (class "Default")
      (node (ref "LED3") (pin "C") (pinfunction "C_C") (pintype "passive"))
      (node (ref "R6") (pin "2") (pinfunction "2_2") (pintype "passive"))
    )
    (net (code "81") (name "Net-(R16-Pad2)") (class "Default")
      (node (ref "R16") (pin "2") (pinfunction "2_2") (pintype "passive"))
      (node (ref "U6") (pin "63") (pinfunction "63_63") (pintype "bidirectional"))
    )
    (net (code "82") (name "Net-(RG2-Pad1)") (class "Default")
      (node (ref "RG2") (pin "1") (pinfunction "1_1") (pintype "passive"))
      (node (ref "RG3") (pin "2") (pinfunction "2_2") (pintype "passive"))
      (node (ref "TEMP2") (pin "1") (pinfunction "1_1") (pintype "passive"))
    )
    (net (code "83") (name "Net-(U$1-FB)") (class "Default")
      (node (ref "R3") (pin "1") (pinfunction "1_1") (pintype "passive"))
      (node (ref "R5") (pin "2") (pinfunction "2_2") (pintype "passive"))
      (node (ref "U$1") (pin "7") (pinfunction "FB_7") (pintype "input"))
    )
    (net (code "84") (name "Net-(U$1-SS)") (class "Default")
      (node (ref "C4") (pin "1") (pinfunction "1_1") (pintype "passive"))
      (node (ref "U$1") (pin "6") (pinfunction "SS_6") (pintype "input"))
    )
    (net (code "85") (name "Net-(U1-*CHG)") (class "Default")
      (node (ref "LED1") (pin "C") (pinfunction "C_C") (pintype "passive"))
      (node (ref "U1") (pin "8") (pinfunction "*CHG_8") (pintype "output"))
    )
    (net (code "86") (name "Net-(U1-*PG)") (class "Default")
      (node (ref "LED2") (pin "C") (pinfunction "C_C") (pintype "passive"))
      (node (ref "U1") (pin "6") (pinfunction "*PG_6") (pintype "output"))
    )
    (net (code "87") (name "Net-(U1-ISET)") (class "Default")
      (node (ref "R4") (pin "2") (pinfunction "2_2") (pintype "passive"))
      (node (ref "U1") (pin "2") (pinfunction "ISET_2") (pintype "input"))
    )
    (net (code "88") (name "Net-(U1-TS)") (class "Default")
      (node (ref "RT1") (pin "1") (pinfunction "1_1") (pintype "passive"))
      (node (ref "TEMP1") (pin "2") (pinfunction "2_2") (pintype "passive"))
      (node (ref "U1") (pin "5") (pinfunction "TS_5") (pintype "input"))
    )
    (net (code "89") (name "Net-(U1-VDPM)") (class "Default")
      (node (ref "RVDM") (pin "2") (pinfunction "2_2") (pintype "passive"))
      (node (ref "U1") (pin "9") (pinfunction "VDPM_9") (pintype "input"))
    )
    (net (code "90") (name "Net-(U1-VTSB)") (class "Default")
      (node (ref "RT1") (pin "2") (pinfunction "2_2") (pintype "passive"))
      (node (ref "U1") (pin "4") (pinfunction "VTSB_4") (pintype "output"))
    )
    (net (code "91") (name "Net-(U2-BI{slash}TOUT)") (class "Default")
      (node (ref "CG2") (pin "1") (pinfunction "1_1") (pintype "passive"))
      (node (ref "RG1") (pin "1") (pinfunction "1_1") (pintype "passive"))
      (node (ref "RG2") (pin "2") (pinfunction "2_2") (pintype "passive"))
      (node (ref "U2") (pin "1") (pinfunction "BI/TOUT_1") (pintype "bidirectional"))
    )
    (net (code "92") (name "Net-(U2-REG25)") (class "Default")
      (node (ref "CG4") (pin "1") (pinfunction "1_1") (pintype "passive"))
      (node (ref "RG1") (pin "2") (pinfunction "2_2") (pintype "passive"))
      (node (ref "U2") (pin "2") (pinfunction "REG25_2") (pintype "power_in"))
      (node (ref "U2") (pin "5") (pinfunction "VCC_5") (pintype "power_in"))
    )
    (net (code "93") (name "Net-(U2-SRN)") (class "Default")
      (node (ref "CG6") (pin "1") (pinfunction "1_1") (pintype "passive"))
      (node (ref "CG7") (pin "1") (pinfunction "1_1") (pintype "passive"))
      (node (ref "RG5") (pin "2") (pinfunction "2_2") (pintype "passive"))
      (node (ref "U2") (pin "8") (pinfunction "SRN_8") (pintype "input"))
    )
    (net (code "94") (name "Net-(U2-SRP)") (class "Default")
      (node (ref "CG6") (pin "2") (pinfunction "2_2") (pintype "passive"))
      (node (ref "CG8") (pin "2") (pinfunction "2_2") (pintype "passive"))
      (node (ref "RG6") (pin "2") (pinfunction "2_2") (pintype "passive"))
      (node (ref "U2") (pin "7") (pinfunction "SRP_7") (pintype "input"))
    )
    (net (code "95") (name "Net-(U2-TS)") (class "Default")
      (node (ref "CG1") (pin "1") (pinfunction "1_1") (pintype "passive"))
      (node (ref "RG3") (pin "1") (pinfunction "1_1") (pintype "passive"))
      (node (ref "U2") (pin "9") (pinfunction "TS_9") (pintype "input"))
    )
    (net (code "96") (name "Net-(U3-AOUT1)") (class "Default")
      (node (ref "SV1") (pin "1") (pinfunction "1_1") (pintype "passive"))
      (node (ref "U3") (pin "2") (pinfunction "AOUT1_2") (pintype "output"))
    )
    (net (code "97") (name "Net-(U3-AOUT2)") (class "Default")
      (node (ref "SV1") (pin "2") (pinfunction "2_2") (pintype "passive"))
      (node (ref "U3") (pin "3") (pinfunction "AOUT2_3") (pintype "output"))
    )
    (net (code "98") (name "Net-(U3-BOUT1)") (class "Default")
      (node (ref "SV1") (pin "3") (pinfunction "3_3") (pintype "passive"))
      (node (ref "U3") (pin "4") (pinfunction "BOUT1_4") (pintype "output"))
    )
    (net (code "99") (name "Net-(U3-BOUT2)") (class "Default")
      (node (ref "SV1") (pin "4") (pinfunction "4_4") (pintype "passive"))
      (node (ref "U3") (pin "5") (pinfunction "BOUT2_5") (pintype "output"))
    )
    (net (code "100") (name "Net-(U4-AOUT1)") (class "Default")
      (node (ref "SV2") (pin "1") (pinfunction "1_1") (pintype "passive"))
      (node (ref "U4") (pin "2") (pinfunction "AOUT1_2") (pintype "output"))
    )
    (net (code "101") (name "Net-(U4-AOUT2)") (class "Default")
      (node (ref "SV2") (pin "2") (pinfunction "2_2") (pintype "passive"))
      (node (ref "U4") (pin "3") (pinfunction "AOUT2_3") (pintype "output"))
    )
    (net (code "102") (name "Net-(U4-BOUT1)") (class "Default")
      (node (ref "SV2") (pin "3") (pinfunction "3_3") (pintype "passive"))
      (node (ref "U4") (pin "4") (pinfunction "BOUT1_4") (pintype "output"))
    )
    (net (code "103") (name "Net-(U4-BOUT2)") (class "Default")
      (node (ref "SV2") (pin "4") (pinfunction "4_4") (pintype "passive"))
      (node (ref "U4") (pin "5") (pinfunction "BOUT2_5") (pintype "output"))
    )
    (net (code "104") (name "Net-(U5-AOUT1)") (class "Default")
      (node (ref "SV3") (pin "1") (pinfunction "1_1") (pintype "passive"))
      (node (ref "U5") (pin "2") (pinfunction "AOUT1_2") (pintype "output"))
    )
    (net (code "105") (name "Net-(U5-AOUT2)") (class "Default")
      (node (ref "SV3") (pin "2") (pinfunction "2_2") (pintype "passive"))
      (node (ref "U5") (pin "3") (pinfunction "AOUT2_3") (pintype "output"))
    )
    (net (code "106") (name "Net-(U5-BOUT1)") (class "Default")
      (node (ref "SV3") (pin "3") (pinfunction "3_3") (pintype "passive"))
      (node (ref "U5") (pin "4") (pinfunction "BOUT1_4") (pintype "output"))
    )
    (net (code "107") (name "Net-(U5-BOUT2)") (class "Default")
      (node (ref "SV3") (pin "4") (pinfunction "4_4") (pintype "passive"))
      (node (ref "U5") (pin "5") (pinfunction "BOUT2_5") (pintype "output"))
    )
    (net (code "108") (name "Net-(U7-AOUT1)") (class "Default")
      (node (ref "SV4") (pin "1") (pinfunction "1_1") (pintype "passive"))
      (node (ref "U7") (pin "2") (pinfunction "AOUT1_2") (pintype "output"))
    )
    (net (code "109") (name "Net-(U7-AOUT2)") (class "Default")
      (node (ref "SV4") (pin "2") (pinfunction "2_2") (pintype "passive"))
      (node (ref "U7") (pin "3") (pinfunction "AOUT2_3") (pintype "output"))
    )
    (net (code "110") (name "Net-(U7-BOUT1)") (class "Default")
      (node (ref "SV4") (pin "3") (pinfunction "3_3") (pintype "passive"))
      (node (ref "U7") (pin "4") (pinfunction "BOUT1_4") (pintype "output"))
    )
    (net (code "111") (name "Net-(U7-BOUT2)") (class "Default")
      (node (ref "SV4") (pin "4") (pinfunction "4_4") (pintype "passive"))
      (node (ref "U7") (pin "5") (pinfunction "BOUT2_5") (pintype "output"))
    )
    (net (code "112") (name "VCC") (class "Default")
      (node (ref "C1") (pin "1") (pinfunction "1_1") (pintype "passive"))
      (node (ref "SOLAR") (pin "2") (pinfunction "2_2") (pintype "passive"))
      (node (ref "T1") (pin "3") (pinfunction "C_3") (pintype "passive"))
      (node (ref "U1") (pin "1") (pinfunction "VBUS_1") (pintype "bidirectional"))
    )
    (net (code "113") (name "unconnected-(COMPASS-DRDY-Pad15)") (class "Default")
      (node (ref "COMPASS") (pin "15") (pinfunction "DRDY_15") (pintype "input"))
    )
    (net (code "114") (name "unconnected-(IC2-Pad6)") (class "Default")
      (node (ref "IC2") (pin "6") (pinfunction "6_6") (pintype "bidirectional"))
    )
    (net (code "115") (name "unconnected-(IC2-Pad7)") (class "Default")
      (node (ref "IC2") (pin "7") (pinfunction "7_7") (pintype "bidirectional"))
    )
    (net (code "116") (name "unconnected-(IC2-Pad12)") (class "Default")
      (node (ref "IC2") (pin "12") (pinfunction "12_12") (pintype "bidirectional"))
    )
    (net (code "117") (name "unconnected-(IC2-Pad22)") (class "Default")
      (node (ref "IC2") (pin "22") (pinfunction "22_22") (pintype "bidirectional"))
    )
    (net (code "118") (name "unconnected-(U$1-HYS-Pad8)") (class "Default")
      (node (ref "U$1") (pin "8") (pinfunction "HYS_8") (pintype "input"))
    )
    (net (code "119") (name "unconnected-(U2-BAT_LOW{slash}BAT_GD-Pad12)") (class "Default")
      (node (ref "U2") (pin "12") (pinfunction "BAT_LOW/BAT_GD_12") (pintype "output"))
    )
    (net (code "120") (name "unconnected-(U6-Pad5)") (class "Default")
      (node (ref "U6") (pin "5") (pinfunction "5_5") (pintype "bidirectional"))
    )
    (net (code "121") (name "unconnected-(U6-Pad6)") (class "Default")
      (node (ref "U6") (pin "6") (pinfunction "6_6") (pintype "bidirectional"))
    )
    (net (code "122") (name "unconnected-(U6-Pad7)") (class "Default")
      (node (ref "U6") (pin "7") (pinfunction "7_7") (pintype "bidirectional"))
    )
    (net (code "123") (name "unconnected-(U6-Pad8)") (class "Default")
      (node (ref "U6") (pin "8") (pinfunction "8_8") (pintype "bidirectional"))
    )
    (net (code "124") (name "unconnected-(U6-Pad62)") (class "Default")
      (node (ref "U6") (pin "62") (pinfunction "62_62") (pintype "bidirectional"))
    )
    (net (code "125") (name "unconnected-(U6-Pad64)") (class "Default")
      (node (ref "U6") (pin "64") (pinfunction "64_64") (pintype "bidirectional"))
    )
    (net (code "126") (name "unconnected-(U6-Pad69)") (class "Default")
      (node (ref "U6") (pin "69") (pinfunction "69_69") (pintype "bidirectional"))
    )
    (net (code "127") (name "unconnected-(U6-Pad70)") (class "Default")
      (node (ref "U6") (pin "70") (pinfunction "70_70") (pintype "bidirectional"))
    )
    (net (code "128") (name "unconnected-(U6-Pad72)") (class "Default")
      (node (ref "U6") (pin "72") (pinfunction "72_72") (pintype "bidirectional"))
    )
    (net (code "129") (name "unconnected-(U6-Pad73)") (class "Default")
      (node (ref "U6") (pin "73") (pinfunction "73_73") (pintype "bidirectional"))
    )
    (net (code "130") (name "unconnected-(U6-Pad74)") (class "Default")
      (node (ref "U6") (pin "74") (pinfunction "74_74") (pintype "bidirectional"))
    )
    (net (code "131") (name "unconnected-(U6-Pad75)") (class "Default")
      (node (ref "U6") (pin "75") (pinfunction "75_75") (pintype "bidirectional"))
    )
  )
)
